# easyeda.net
KiCad netlist of a schematic drawn in EasyEDA
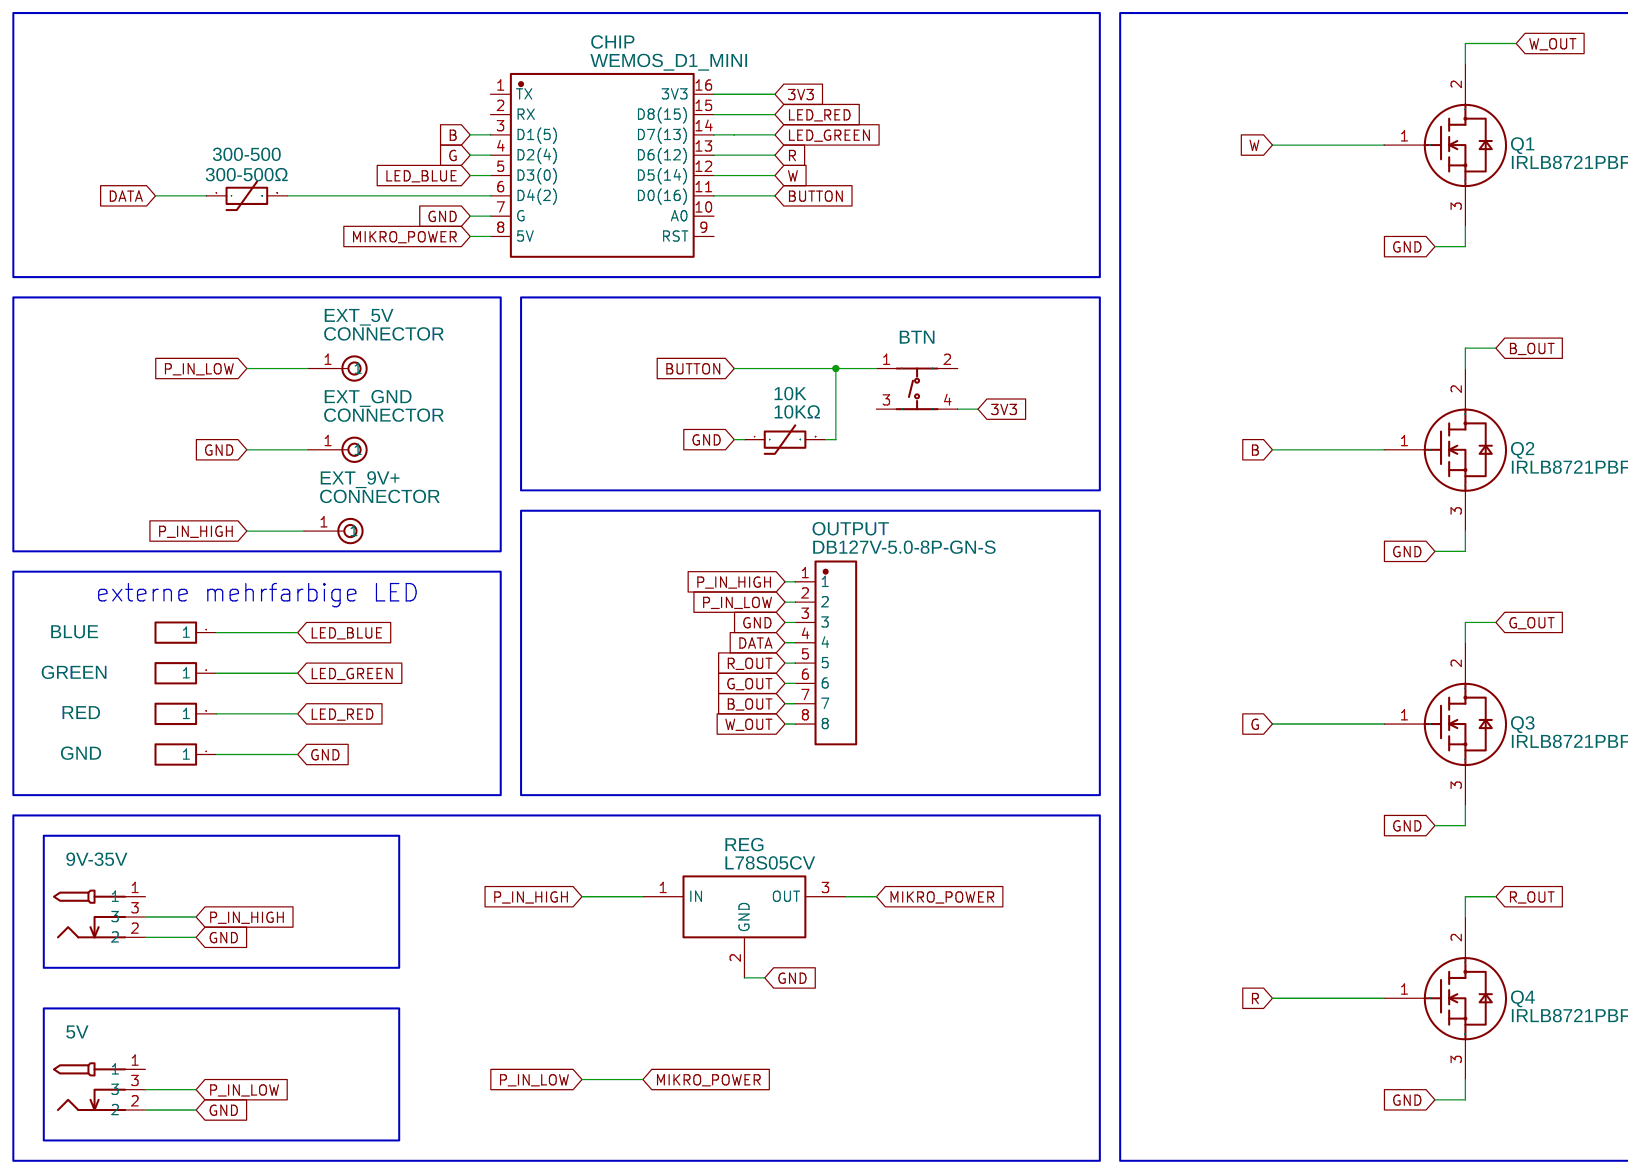
[diagram p0: schematic sheet]

(export (version "E")
  (design (tool "Eeschema 10.0.6"))
  (components
    (comp (ref "5V")
      (value "IN")
      (fields
        (field (name "BOM_Manufacturer Part") "DC-005 5.5-2.0MM")
        (field (name "BOM_Supplier Part") "C16214")
      )
      (libsource (lib "") (part "DC-005 5.5-2.0MM"))
    )
    (comp (ref "9V-35V")
      (value "IN")
      (fields
        (field (name "BOM_Manufacturer Part") "DC-005 5.5-2.0MM")
        (field (name "BOM_Supplier Part") "C16214")
      )
      (libsource (lib "") (part "DC-005 5.5-2.0MM_1"))
    )
    (comp (ref "10K")
      (value "10KΩ")
      (fields
        (field (name "BOM_Manufacturer Part") "MF58 103F3950")
        (field (name "BOM_Supplier Part") "C123393")
      )
      (libsource (lib "") (part "10KΩ ±1%_MF58"))
    )
    (comp (ref "300-500")
      (value "300-500Ω")
      (fields
        (field (name "BOM_Manufacturer Part") "MF58 103F3950")
        (field (name "BOM_Supplier Part") "C123393")
      )
      (libsource (lib "") (part "10KΩ ±1%_MF58_1"))
    )
    (comp (ref "BLUE")
      (value "BUZZER-DATA")
      (fields (field (name "BOM_Supplier Part") "C81276"))
      (libsource (lib "") (part "HDR-M-2.54_1x1_1"))
    )
    (comp (ref "BTN")
      (value "BTN")
      (fields
        (field (name "BOM_Manufacturer Part") "TSW101G232-250Z")
        (field (name "BOM_Supplier Part") "C326507")
      )
      (libsource (lib "") (part "TSW101G232-250Z"))
    )
    (comp (ref "CHIP")
      (value "WEMOS_D1_MINI")
      (fields
        (field (name "BOM_Manufacturer Part") "Wemos_D1_mini_Pro4")
        (field (name "BOM_Supplier Part") "C2837266")
      )
      (libsource (lib "") (part "WEMOS_D1_MINI_PRO4"))
    )
    (comp (ref "EXT_5V") (value "CONNECTOR") (libsource (lib "") (part "HOLE COPY")))
    (comp (ref "EXT_9V+") (value "CONNECTOR") (libsource (lib "") (part "HOLE COPY_2")))
    (comp (ref "EXT_GND") (value "CONNECTOR") (libsource (lib "") (part "HOLE COPY_1")))
    (comp (ref "GND")
      (value "BUZZER-DATA")
      (fields (field (name "BOM_Supplier Part") "C81276"))
      (libsource (lib "") (part "HDR-M-2.54_1x1_2"))
    )
    (comp (ref "GREEN")
      (value "BUZZER-DATA")
      (fields (field (name "BOM_Supplier Part") "C81276"))
      (libsource (lib "") (part "HDR-M-2.54_1x1"))
    )
    (comp (ref "OUTPUT")
      (value "DB127V-5.0-8P-GN-S")
      (fields (field (name "BOM_Supplier Part") "C430626"))
      (libsource (lib "") (part "DB127V-5.0-8P-GN-S"))
    )
    (comp (ref "Q1")
      (value "IRLB8721PBF")
      (fields (field (name "BOM_Supplier Part") "C153222"))
      (libsource (lib "") (part "IRLB8721PBF"))
    )
    (comp (ref "Q2")
      (value "IRLB8721PBF")
      (fields (field (name "BOM_Supplier Part") "C153222"))
      (libsource (lib "") (part "IRLB8721PBF"))
    )
    (comp (ref "Q3")
      (value "IRLB8721PBF")
      (fields (field (name "BOM_Supplier Part") "C153222"))
      (libsource (lib "") (part "IRLB8721PBF"))
    )
    (comp (ref "Q4")
      (value "IRLB8721PBF")
      (fields (field (name "BOM_Supplier Part") "C153222"))
      (libsource (lib "") (part "IRLB8721PBF"))
    )
    (comp (ref "RED")
      (value "BUZZER-DATA")
      (fields (field (name "BOM_Supplier Part") "C81276"))
      (libsource (lib "") (part "HDR-M-2.54_1x1_3"))
    )
    (comp (ref "REG")
      (value "L78S05CV")
      (fields (field (name "BOM_Supplier Part") "C33043"))
      (libsource (lib "") (part "L78S05CV"))
    )
  )
  (nets
    (net (code "1") (name "3V3") (class "Default")
      (node (ref "BTN") (pin "4") (pinfunction "4_4") (pintype "unspecified"))
      (node (ref "CHIP") (pin "16") (pinfunction "3V3_16") (pintype "unspecified"))
    )
    (net (code "2") (name "B") (class "Default")
      (node (ref "CHIP") (pin "3") (pinfunction "D1(5)_3") (pintype "unspecified"))
      (node (ref "Q2") (pin "1") (pinfunction "G_1") (pintype "unspecified"))
    )
    (net (code "3") (name "BUTTON") (class "Default")
      (node (ref "10K") (pin "2") (pinfunction "2_2") (pintype "unspecified"))
      (node (ref "BTN") (pin "1") (pinfunction "1_1") (pintype "unspecified"))
      (node (ref "CHIP") (pin "11") (pinfunction "D0(16)_11") (pintype "unspecified"))
    )
    (net (code "4") (name "B_OUT") (class "Default")
      (node (ref "OUTPUT") (pin "7") (pinfunction "7_7") (pintype "unspecified"))
      (node (ref "Q2") (pin "2") (pinfunction "D_2") (pintype "unspecified"))
    )
    (net (code "5") (name "DATA") (class "Default")
      (node (ref "300-500") (pin "1") (pinfunction "1_1") (pintype "unspecified"))
      (node (ref "OUTPUT") (pin "4") (pinfunction "4_4") (pintype "unspecified"))
    )
    (net (code "6") (name "G") (class "Default")
      (node (ref "CHIP") (pin "4") (pinfunction "D2(4)_4") (pintype "unspecified"))
      (node (ref "Q3") (pin "1") (pinfunction "G_1") (pintype "unspecified"))
    )
    (net (code "7") (name "GND") (class "Default")
      (node (ref "10K") (pin "1") (pinfunction "1_1") (pintype "unspecified"))
      (node (ref "5V") (pin "2") (pinfunction "2_2") (pintype "unspecified"))
      (node (ref "9V-35V") (pin "2") (pinfunction "2_2") (pintype "unspecified"))
      (node (ref "CHIP") (pin "7") (pinfunction "G_7") (pintype "unspecified"))
      (node (ref "EXT_GND") (pin "1") (pinfunction "1_1") (pintype "unspecified"))
      (node (ref "GND") (pin "1") (pinfunction "1_1") (pintype "input"))
      (node (ref "OUTPUT") (pin "3") (pinfunction "3_3") (pintype "unspecified"))
      (node (ref "Q1") (pin "3") (pinfunction "S_3") (pintype "unspecified"))
      (node (ref "Q2") (pin "3") (pinfunction "S_3") (pintype "unspecified"))
      (node (ref "Q3") (pin "3") (pinfunction "S_3") (pintype "unspecified"))
      (node (ref "Q4") (pin "3") (pinfunction "S_3") (pintype "unspecified"))
      (node (ref "REG") (pin "2") (pinfunction "GND_2") (pintype "passive"))
    )
    (net (code "8") (name "G_OUT") (class "Default")
      (node (ref "OUTPUT") (pin "6") (pinfunction "6_6") (pintype "unspecified"))
      (node (ref "Q3") (pin "2") (pinfunction "D_2") (pintype "unspecified"))
    )
    (net (code "9") (name "LED_BLUE") (class "Default")
      (node (ref "BLUE") (pin "1") (pinfunction "1_1") (pintype "input"))
      (node (ref "CHIP") (pin "5") (pinfunction "D3(0)_5") (pintype "unspecified"))
    )
    (net (code "10") (name "LED_GREEN") (class "Default")
      (node (ref "CHIP") (pin "14") (pinfunction "D7(13)_14") (pintype "unspecified"))
      (node (ref "GREEN") (pin "1") (pinfunction "1_1") (pintype "input"))
    )
    (net (code "11") (name "LED_RED") (class "Default")
      (node (ref "CHIP") (pin "15") (pinfunction "D8(15)_15") (pintype "unspecified"))
      (node (ref "RED") (pin "1") (pinfunction "1_1") (pintype "input"))
    )
    (net (code "12") (name "MIKRO_POWER") (class "Default")
      (node (ref "5V") (pin "3") (pinfunction "3_3") (pintype "unspecified"))
      (node (ref "CHIP") (pin "8") (pinfunction "5V_8") (pintype "unspecified"))
      (node (ref "EXT_5V") (pin "1") (pinfunction "1_1") (pintype "unspecified"))
      (node (ref "OUTPUT") (pin "2") (pinfunction "2_2") (pintype "unspecified"))
      (node (ref "REG") (pin "3") (pinfunction "OUT_3") (pintype "passive"))
    )
    (net (code "13") (name "Net-(CHIP-D4(2))") (class "Default")
      (node (ref "300-500") (pin "2") (pinfunction "2_2") (pintype "unspecified"))
      (node (ref "CHIP") (pin "6") (pinfunction "D4(2)_6") (pintype "unspecified"))
    )
    (net (code "14") (name "P_IN_HIGH") (class "Default")
      (node (ref "9V-35V") (pin "3") (pinfunction "3_3") (pintype "unspecified"))
      (node (ref "EXT_9V+") (pin "1") (pinfunction "1_1") (pintype "unspecified"))
      (node (ref "OUTPUT") (pin "1") (pinfunction "1_1") (pintype "unspecified"))
      (node (ref "REG") (pin "1") (pinfunction "IN_1") (pintype "passive"))
    )
    (net (code "15") (name "R") (class "Default")
      (node (ref "CHIP") (pin "13") (pinfunction "D6(12)_13") (pintype "unspecified"))
      (node (ref "Q4") (pin "1") (pinfunction "G_1") (pintype "unspecified"))
    )
    (net (code "16") (name "R_OUT") (class "Default")
      (node (ref "OUTPUT") (pin "5") (pinfunction "5_5") (pintype "unspecified"))
      (node (ref "Q4") (pin "2") (pinfunction "D_2") (pintype "unspecified"))
    )
    (net (code "17") (name "W") (class "Default")
      (node (ref "CHIP") (pin "12") (pinfunction "D5(14)_12") (pintype "unspecified"))
      (node (ref "Q1") (pin "1") (pinfunction "G_1") (pintype "unspecified"))
    )
    (net (code "18") (name "W_OUT") (class "Default")
      (node (ref "OUTPUT") (pin "8") (pinfunction "8_8") (pintype "unspecified"))
      (node (ref "Q1") (pin "2") (pinfunction "D_2") (pintype "unspecified"))
    )
    (net (code "19") (name "unconnected-(5V-Pad1)") (class "Default")
      (node (ref "5V") (pin "1") (pinfunction "1_1") (pintype "unspecified"))
    )
    (net (code "20") (name "unconnected-(9V-35V-Pad1)") (class "Default")
      (node (ref "9V-35V") (pin "1") (pinfunction "1_1") (pintype "unspecified"))
    )
    (net (code "21") (name "unconnected-(BTN-Pad2)") (class "Default")
      (node (ref "BTN") (pin "2") (pinfunction "2_2") (pintype "unspecified"))
    )
    (net (code "22") (name "unconnected-(BTN-Pad3)") (class "Default")
      (node (ref "BTN") (pin "3") (pinfunction "3_3") (pintype "unspecified"))
    )
    (net (code "23") (name "unconnected-(CHIP-A0-Pad10)") (class "Default")
      (node (ref "CHIP") (pin "10") (pinfunction "A0_10") (pintype "unspecified"))
    )
    (net (code "24") (name "unconnected-(CHIP-RST-Pad9)") (class "Default")
      (node (ref "CHIP") (pin "9") (pinfunction "RST_9") (pintype "unspecified"))
    )
    (net (code "25") (name "unconnected-(CHIP-RX-Pad2)") (class "Default")
      (node (ref "CHIP") (pin "2") (pinfunction "RX_2") (pintype "unspecified"))
    )
    (net (code "26") (name "unconnected-(CHIP-TX-Pad1)") (class "Default")
      (node (ref "CHIP") (pin "1") (pinfunction "TX_1") (pintype "unspecified"))
    )
  )
)
